# Fuente-12V.net
KiCad netlist of a schematic drawn in Altium Designer
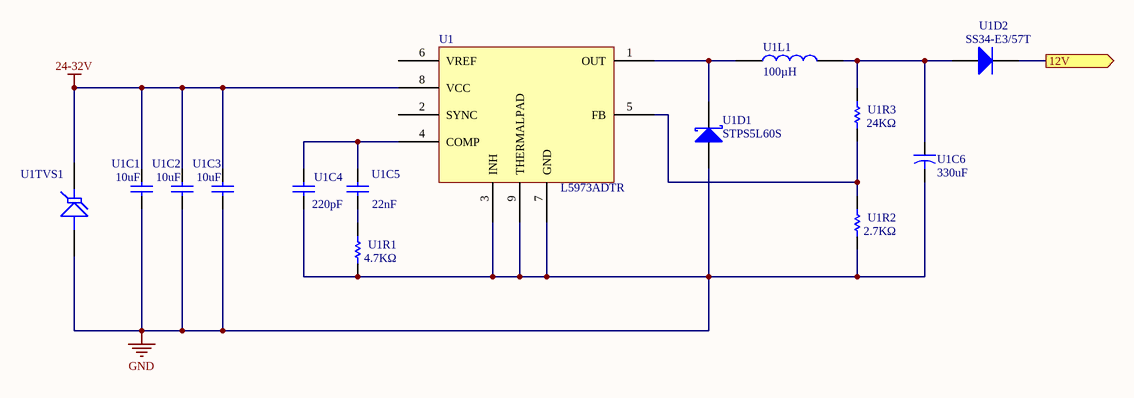
[diagram p0: Fuente-12V.SchDoc]

(export (version "E")
  (design (tool "Eeschema 10.0.6"))
  (components
    (comp (ref "U1")
      (value "L5973ADTR")
      (footprint "SOIC-8-T")
      (description "IC REG SW 2A STEPDOWN 8-SOIC")
      (fields (field (name "MANUFACTURER") "STMicroelectronics"))
      (libsource (lib "*") (part "L5973AD"))
    )
    (comp (ref "U1C1")
      (value "10uF")
      (footprint "1210-CAP")
      (description "CAP CER 10UF 50V Y5V 1210")
      (fields
        (field (name "MANUFACTURER PART NUMBER") "CC1210ZKY5V9BB106")
        (field (name "MANUFACTURER") "Yageo")
      )
      (libsource (lib "*") (part "Cap"))
    )
    (comp (ref "U1C2")
      (value "10uF")
      (footprint "1210-CAP")
      (description "CAP CER 10UF 50V Y5V 1210")
      (fields
        (field (name "MANUFACTURER PART NUMBER") "CC1210ZKY5V9BB106")
        (field (name "MANUFACTURER") "Yageo")
      )
      (libsource (lib "*") (part "Cap"))
    )
    (comp (ref "U1C3")
      (value "10uF")
      (footprint "1210-CAP")
      (description "CAP CER 10UF 50V Y5V 1210")
      (fields
        (field (name "MANUFACTURER PART NUMBER") "CC1210ZKY5V9BB106")
        (field (name "MANUFACTURER") "Yageo")
      )
      (libsource (lib "*") (part "Cap"))
    )
    (comp (ref "U1C4")
      (value "220pF")
      (footprint "1206-CAP")
      (description "CAP CERAMIC 220PF 50V NP0 1206")
      (fields
        (field (name "MANUFACTURER") "Kemet")
        (field (name "MANUFACTURER PART NUMBER") "C1206C221K5GACTU")
      )
      (libsource (lib "*") (part "Cap"))
    )
    (comp (ref "U1C5")
      (value "22nF")
      (footprint "1206-CAP")
      (description "CAP 22000PF 50V CERAMIC X7R 1206")
      (fields
        (field (name "MANUFACTURER") "Kemet")
        (field (name "MANUFACTURER PART NUMBER") "C1206C223K5RACTU")
      )
      (libsource (lib "Miscellaneous Devices") (part "Cap"))
    )
    (comp (ref "U1C6")
      (value "330uF")
      (footprint "CAPPR3.5-8x11.5")
      (description "Capacitor")
      (fields
        (field (name "MANUFACTURER") "PANASONIC ELECTRONIC COMPONENTS")
        (field (name "MANUFACTURER PART NUMBER") "ECA-1EM331B")
      )
      (libsource (lib "Miscellaneous Devices") (part "Cap2"))
    )
    (comp (ref "U1D1")
      (value "STPS5L60S")
      (footprint "DO-214AB")
      (description "DIODE SCHOTTKY 60V 5A SMC")
      (fields
        (field (name "MANUFACTURER PART NUMBER") "B560C-13-F")
        (field (name "MANUFACTURER") "Diodes Incorporated")
      )
      (libsource (lib "*") (part "D Schottky"))
    )
    (comp (ref "U1D2")
      (value "SS34-E3/57T")
      (footprint "DO-214AB")
      (description "DIODE SCHOTTKY 40V 3A SMC")
      (fields
        (field (name "MANUFACTURER PART NUMBER") "B340-13-F")
        (field (name "MANUFACTURER") "Diodes Incorporated")
      )
      (libsource (lib "Miscellaneous Devices") (part "Diode"))
    )
    (comp (ref "U1L1")
      (value "100µH")
      (footprint "1280-IND")
      (description "WE-PD SMD Shielded Power Inductor 100uH")
      (fields
        (field (name "MANUFACTURER PART NUMBER") "74477020")
        (field (name "MANUFACTURER") "Wurth Elektronik")
      )
      (libsource (lib "*") (part "IND"))
    )
    (comp (ref "U1R1")
      (value "4.7KΩ")
      (footprint "1206-RES")
      (description "RES 4.7K OHM 1/4W 5% 1206 SMD")
      (fields
        (field (name "MANUFACTURER PART NUMBER") "CRCW12064K70JNEA")
        (field (name "MANUFACTURER") "Vishay Dale")
      )
      (libsource (lib "Miscellaneous Devices") (part "Res1"))
    )
    (comp (ref "U1R2")
      (value "2.7KΩ")
      (footprint "0805-RES")
      (description "RES 2.70K OHM 1/8W 1% 0805 SMD")
      (fields
        (field (name "MANUFACTURER") "Vishay Dale")
        (field (name "MANUFACTURER PART NUMBER") "CRCW08052K70FKEA")
      )
      (libsource (lib "*") (part "Res1"))
    )
    (comp (ref "U1R3")
      (value "24KΩ")
      (footprint "0805-RES")
      (fields
        (field (name "MANUFACTURER PART NUMBER") "ERA-6AEB3162V")
        (field (name "MANUFACTURER") "Panasonic Electronic Components")
      )
      (libsource (lib "*") (part "Res1"))
    )
    (comp (ref "U1TVS1")
      (value "33V")
      (footprint "DO-15")
      (description "TVS 33 VOLT 600 WATT UNI-DIR TRANZORB")
      (fields
        (field (name "MANUFACTURER PART NUMBER") "P6KE33A")
        (field (name "MANUFACTURER") "Littelfuse Inc.")
      )
      (libsource (lib "Miscellaneous Devices") (part "Tranzorb"))
    )
  )
  (nets
    (net (code "1") (name "/12V") (class "Default")
      (node (ref "U1D2") (pin "2") (pinfunction "K_2") (pintype "passive"))
    )
    (net (code "2") (name "24-32V") (class "Default")
      (node (ref "U1") (pin "8") (pinfunction "VCC_8") (pintype "passive"))
      (node (ref "U1C1") (pin "2") (pinfunction "2_2") (pintype "passive"))
      (node (ref "U1C2") (pin "2") (pinfunction "2_2") (pintype "passive"))
      (node (ref "U1C3") (pin "2") (pinfunction "2_2") (pintype "passive"))
      (node (ref "U1TVS1") (pin "2") (pinfunction "K_2") (pintype "passive"))
    )
    (net (code "3") (name "GND") (class "Default")
      (node (ref "U1") (pin "3") (pinfunction "INH_3") (pintype "passive"))
      (node (ref "U1") (pin "7") (pinfunction "GND_7") (pintype "passive"))
      (node (ref "U1") (pin "9") (pinfunction "THERMALPAD_9") (pintype "passive"))
      (node (ref "U1C1") (pin "1") (pinfunction "1_1") (pintype "passive"))
      (node (ref "U1C2") (pin "1") (pinfunction "1_1") (pintype "passive"))
      (node (ref "U1C3") (pin "1") (pinfunction "1_1") (pintype "passive"))
      (node (ref "U1C4") (pin "1") (pinfunction "1_1") (pintype "passive"))
      (node (ref "U1C6") (pin "2") (pinfunction "2_2") (pintype "passive"))
      (node (ref "U1D1") (pin "1") (pinfunction "A_1") (pintype "passive"))
      (node (ref "U1R1") (pin "1") (pinfunction "1_1") (pintype "passive"))
      (node (ref "U1R2") (pin "2") (pinfunction "2_2") (pintype "passive"))
      (node (ref "U1TVS1") (pin "1") (pinfunction "A_1") (pintype "passive"))
    )
    (net (code "4") (name "Net-(U1-COMP)") (class "Default")
      (node (ref "U1") (pin "4") (pinfunction "COMP_4") (pintype "passive"))
      (node (ref "U1C4") (pin "2") (pinfunction "2_2") (pintype "passive"))
      (node (ref "U1C5") (pin "2") (pinfunction "2_2") (pintype "passive"))
    )
    (net (code "5") (name "Net-(U1-FB)") (class "Default")
      (node (ref "U1") (pin "5") (pinfunction "FB_5") (pintype "passive"))
      (node (ref "U1R2") (pin "1") (pinfunction "1_1") (pintype "passive"))
      (node (ref "U1R3") (pin "2") (pinfunction "2_2") (pintype "passive"))
    )
    (net (code "6") (name "Net-(U1-OUT)") (class "Default")
      (node (ref "U1") (pin "1") (pinfunction "OUT_1") (pintype "passive"))
      (node (ref "U1D1") (pin "2") (pinfunction "K_2") (pintype "passive"))
      (node (ref "U1L1") (pin "1") (pinfunction "1_1") (pintype "passive"))
    )
    (net (code "7") (name "Net-(U1C5-Pad1)") (class "Default")
      (node (ref "U1C5") (pin "1") (pinfunction "1_1") (pintype "passive"))
      (node (ref "U1R1") (pin "2") (pinfunction "2_2") (pintype "passive"))
    )
    (net (code "8") (name "Net-(U1D2-A)") (class "Default")
      (node (ref "U1C6") (pin "1") (pinfunction "1_1") (pintype "passive"))
      (node (ref "U1D2") (pin "1") (pinfunction "A_1") (pintype "passive"))
      (node (ref "U1L1") (pin "2") (pinfunction "2_2") (pintype "passive"))
      (node (ref "U1R3") (pin "1") (pinfunction "1_1") (pintype "passive"))
    )
    (net (code "9") (name "unconnected-(U1-SYNC-Pad2)") (class "Default")
      (node (ref "U1") (pin "2") (pinfunction "SYNC_2") (pintype "passive"))
    )
    (net (code "10") (name "unconnected-(U1-VREF-Pad6)") (class "Default")
      (node (ref "U1") (pin "6") (pinfunction "VREF_6") (pintype "passive"))
    )
  )
)
